# esp32.net
KiCad netlist of a schematic drawn in Altium Designer
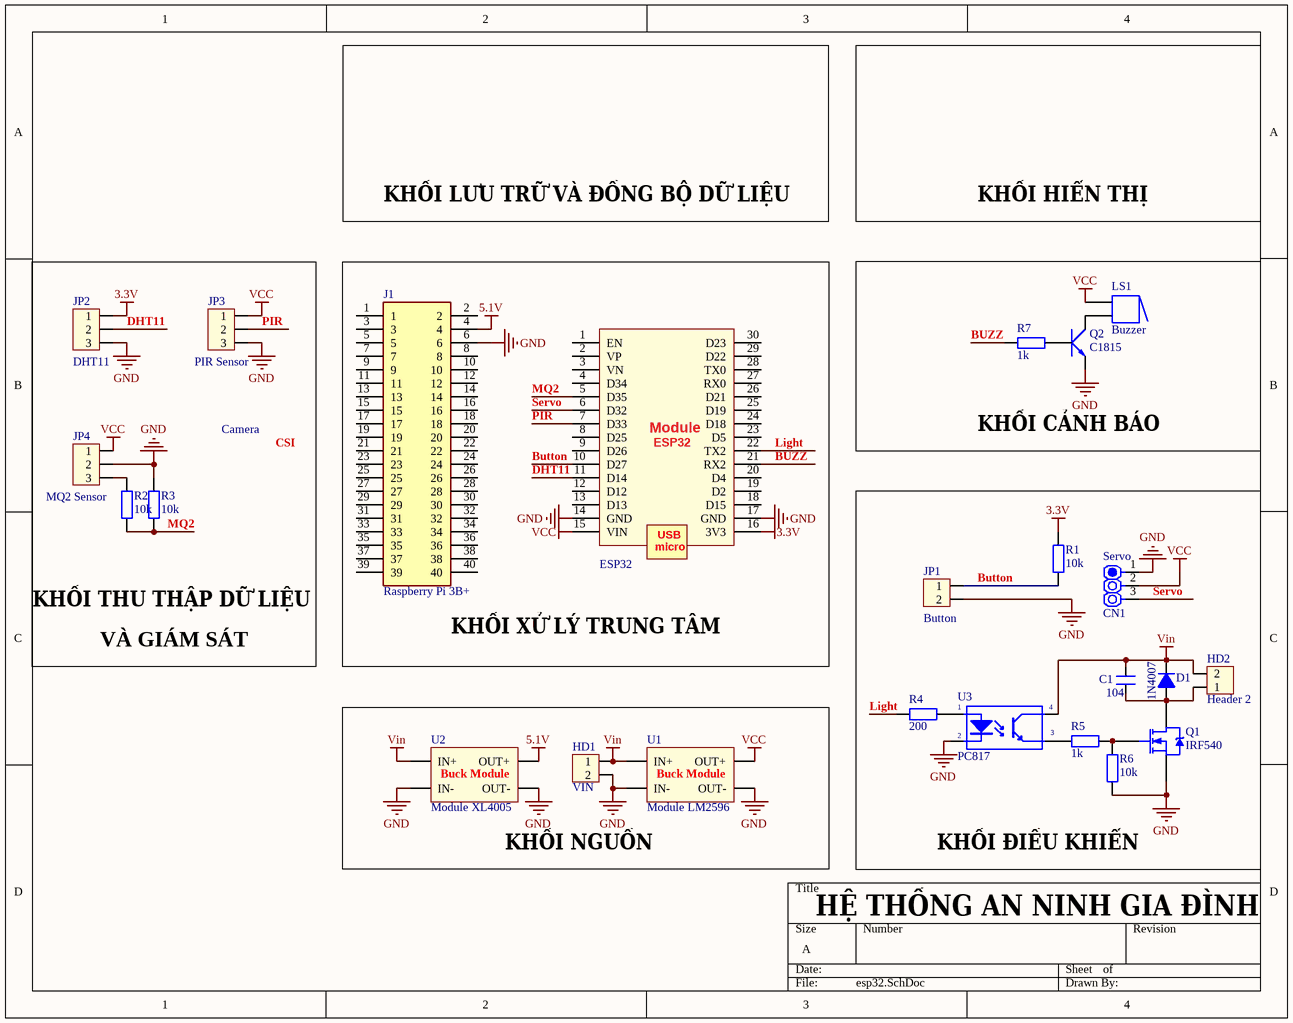
[diagram p0: esp32.SchDoc]

(export (version "E")
  (design (tool "Eeschema 10.0.6"))
  (components
    (comp (ref "C1")
      (value "104")
      (footprint "CN3")
      (description "Cap np W0.3")
      (fields (field (name "COPYRIGHT") "VanDungEvn"))
      (libsource (lib "hphonglib") (part "CN3"))
    )
    (comp (ref "CN1")
      (value "Servo")
      (footprint "CON.HDR1X3")
      (description "Header 1x3")
      (fields (field (name "PUBLISHER") "Hoang Nguyen"))
      (libsource (lib "hphonglib") (part "CON.HDR1x3"))
    )
    (comp (ref "D1")
      (value "1N4007")
      (footprint "D1A")
      (description "Diode 1A")
      (libsource (lib "hphonglib") (part "D1A"))
    )
    (comp (ref "ESP32")
      (value "ESP32_Dev_Module")
      (footprint "ESP32_Dev_Module")
      (libsource (lib "DaoTakIsaac") (part "ESP32_Dev_Module"))
    )
    (comp (ref "HD1")
      (value "VIN")
      (footprint "HED2")
      (description "Header 2 (Green)")
      (libsource (lib "hphonglib") (part "Hed2"))
    )
    (comp (ref "HD2")
      (value "Header 2")
      (footprint "HED2")
      (description "Header 2 (Green)")
      (libsource (lib "") (part "Hed2_1"))
    )
    (comp (ref "J1")
      (value "Raspberry Pi 3B+")
      (footprint "SamacSys:2187")
      (description "Connector")
      (fields (field (name "MANUFACTURER_PART_NUMBER") "2187") (field (name "MOUSER PART NUMBER") "485-2187"))
      (libsource (lib "*") (part "2187"))
    )
    (comp (ref "JP1")
      (value "Button")
      (footprint "CON2")
      (description "Connector 2")
      (libsource (lib "hphonglib") (part "Con2"))
    )
    (comp (ref "JP2")
      (value "DHT11")
      (footprint "CON3")
      (description "Connector 3")
      (libsource (lib "hphonglib") (part "Con3"))
    )
    (comp (ref "JP3")
      (value "PIR Sensor")
      (footprint "CON3")
      (description "Connector 3")
      (libsource (lib "hphonglib") (part "Con3"))
    )
    (comp (ref "JP4")
      (value "MQ2 Sensor")
      (footprint "CON3")
      (description "Connector 3")
      (libsource (lib "hphonglib") (part "Con3"))
    )
    (comp (ref "LS1")
      (value "Buzzer")
      (footprint "Buzzer")
      (description "Magnetic Transducer Buzzer")
      (fields (field (name "PUBLISHER") "Altium Limited"))
      (libsource (lib "hphonglib") (part "Buzzer"))
    )
    (comp (ref "Q1")
      (value "IRF540")
      (footprint "TO-220-3")
      (description "HEXFET N-Channel Power MOSFET")
      (fields (field (name "PUBLISHER") "Altium Limited"))
      (libsource (lib "hphonglib") (part "IRF540"))
    )
    (comp (ref "Q2")
      (value "C1815")
      (footprint "QTO-92")
      (description "NPN 600mW, ECB")
      (libsource (lib "hphonglib") (part "C1815_1"))
    )
    (comp (ref "R1")
      (value "10k")
      (footprint "R1/4W")
      (description "Resistor 1/4W")
      (libsource (lib "hphonglib") (part "R1/4W"))
    )
    (comp (ref "R2")
      (value "10k")
      (footprint "R1/4W")
      (description "Resistor 1/4W")
      (libsource (lib "hphonglib") (part "R1/4W"))
    )
    (comp (ref "R3")
      (value "10k")
      (footprint "R1/4W")
      (description "Resistor 1/4W")
      (libsource (lib "hphonglib") (part "R1/4W"))
    )
    (comp (ref "R4")
      (value "200")
      (footprint "R1/4W")
      (description "Resistor 1/4W")
      (libsource (lib "hphonglib") (part "R1/4W"))
    )
    (comp (ref "R5")
      (value "1k")
      (footprint "R1/4W")
      (description "Resistor 1/4W")
      (libsource (lib "hphonglib") (part "R1/4W"))
    )
    (comp (ref "R6")
      (value "10k")
      (footprint "R1/4W")
      (description "Resistor 1/4W")
      (libsource (lib "hphonglib") (part "R1/4W"))
    )
    (comp (ref "R7")
      (value "1k")
      (footprint "R1/4W")
      (description "Resistor 1/4W")
      (libsource (lib "hphonglib") (part "R1/4W"))
    )
    (comp (ref "U1")
      (value "Module LM2596")
      (footprint "Buck LM2596 Module")
      (description "Buck Module")
      (libsource (lib "DaoTakIsaac") (part "Buck_Module"))
    )
    (comp (ref "U2")
      (value "Module XL4005")
      (footprint "Buck XL4015 Module")
      (description "Buck Module")
      (libsource (lib "DaoTakIsaac") (part "Buck_Module"))
    )
    (comp (ref "U3")
      (value "PC817")
      (footprint "DIP4/W0.3")
      (description "Single Opto")
      (libsource (lib "hphonglib") (part "PC817_1"))
    )
  )
  (nets
    (net (code "1") (name "/BUZZ") (class "Default")
      (node (ref "ESP32") (pin "21") (pinfunction "RX2_21") (pintype "passive"))
      (node (ref "R7") (pin "1") (pinfunction "1_1") (pintype "passive"))
    )
    (net (code "2") (name "/Button") (class "Default")
      (node (ref "ESP32") (pin "10") (pinfunction "D27_10") (pintype "passive"))
      (node (ref "JP1") (pin "1") (pinfunction "1_1") (pintype "passive"))
      (node (ref "R1") (pin "1") (pinfunction "1_1") (pintype "passive"))
    )
    (net (code "4") (name "/DHT11") (class "Default")
      (node (ref "ESP32") (pin "11") (pinfunction "D14_11") (pintype "passive"))
      (node (ref "JP2") (pin "2") (pinfunction "2_2") (pintype "passive"))
    )
    (net (code "5") (name "/Light") (class "Default")
      (node (ref "ESP32") (pin "22") (pinfunction "TX2_22") (pintype "passive"))
      (node (ref "R4") (pin "1") (pinfunction "1_1") (pintype "passive"))
    )
    (net (code "6") (name "/MQ2") (class "Default")
      (node (ref "ESP32") (pin "5") (pinfunction "D35_5") (pintype "passive"))
      (node (ref "R2") (pin "1") (pinfunction "1_1") (pintype "passive"))
      (node (ref "R3") (pin "1") (pinfunction "1_1") (pintype "passive"))
    )
    (net (code "7") (name "/PIR") (class "Default")
      (node (ref "ESP32") (pin "7") (pinfunction "D33_7") (pintype "passive"))
      (node (ref "JP3") (pin "2") (pinfunction "2_2") (pintype "passive"))
    )
    (net (code "8") (name "/Servo") (class "Default")
      (node (ref "CN1") (pin "3") (pinfunction "3_3") (pintype "passive"))
      (node (ref "ESP32") (pin "6") (pinfunction "D32_6") (pintype "passive"))
    )
    (net (code "9") (name "3.3V") (class "Default")
      (node (ref "ESP32") (pin "16") (pinfunction "3V3_16") (pintype "passive"))
      (node (ref "JP2") (pin "1") (pinfunction "1_1") (pintype "passive"))
      (node (ref "R1") (pin "2") (pinfunction "2_2") (pintype "passive"))
    )
    (net (code "10") (name "5.1V") (class "Default")
      (node (ref "J1") (pin "4") (pinfunction "4_4") (pintype "passive"))
      (node (ref "U2") (pin "2") (pinfunction "OUT+_2") (pintype "passive"))
    )
    (net (code "11") (name "GND") (class "Default")
      (node (ref "CN1") (pin "1") (pinfunction "1_1") (pintype "passive"))
      (node (ref "ESP32") (pin "14") (pinfunction "GND_14") (pintype "passive"))
      (node (ref "ESP32") (pin "17") (pinfunction "GND_17") (pintype "passive"))
      (node (ref "HD1") (pin "2") (pinfunction "2_2") (pintype "passive"))
      (node (ref "J1") (pin "6") (pinfunction "6_6") (pintype "passive"))
      (node (ref "JP1") (pin "2") (pinfunction "2_2") (pintype "passive"))
      (node (ref "JP2") (pin "3") (pinfunction "3_3") (pintype "passive"))
      (node (ref "JP3") (pin "3") (pinfunction "3_3") (pintype "passive"))
      (node (ref "JP4") (pin "2") (pinfunction "2_2") (pintype "passive"))
      (node (ref "Q1") (pin "3") (pinfunction "S_3") (pintype "passive"))
      (node (ref "Q2") (pin "1") (pinfunction "E_1") (pintype "passive"))
      (node (ref "R3") (pin "2") (pinfunction "2_2") (pintype "passive"))
      (node (ref "R6") (pin "1") (pinfunction "1_1") (pintype "passive"))
      (node (ref "U1") (pin "3") (pinfunction "IN-_3") (pintype "passive"))
      (node (ref "U1") (pin "4") (pinfunction "OUT-_4") (pintype "passive"))
      (node (ref "U2") (pin "3") (pinfunction "IN-_3") (pintype "passive"))
      (node (ref "U2") (pin "4") (pinfunction "OUT-_4") (pintype "passive"))
      (node (ref "U3") (pin "2") (pinfunction "K_2") (pintype "passive"))
    )
    (net (code "12") (name "Net-(D1-A)") (class "Default")
      (node (ref "C1") (pin "1") (pinfunction "1_1") (pintype "passive"))
      (node (ref "D1") (pin "1") (pinfunction "A_1") (pintype "passive"))
      (node (ref "HD2") (pin "1") (pinfunction "1_1") (pintype "passive"))
      (node (ref "Q1") (pin "2") (pinfunction "D_2") (pintype "passive"))
    )
    (net (code "13") (name "Net-(JP4-Pad3)") (class "Default")
      (node (ref "JP4") (pin "3") (pinfunction "3_3") (pintype "passive"))
      (node (ref "R2") (pin "2") (pinfunction "2_2") (pintype "passive"))
    )
    (net (code "14") (name "Net-(Q1-G)") (class "Default")
      (node (ref "Q1") (pin "1") (pinfunction "G_1") (pintype "passive"))
      (node (ref "R5") (pin "2") (pinfunction "2_2") (pintype "passive"))
      (node (ref "R6") (pin "2") (pinfunction "2_2") (pintype "passive"))
    )
    (net (code "15") (name "Net-(Q2-B)") (class "Default")
      (node (ref "Q2") (pin "3") (pinfunction "B_3") (pintype "passive"))
      (node (ref "R7") (pin "2") (pinfunction "2_2") (pintype "passive"))
    )
    (net (code "16") (name "Net-(Q2-C)") (class "Default")
      (node (ref "LS1") (pin "2") (pinfunction "2_2") (pintype "passive"))
      (node (ref "Q2") (pin "2") (pinfunction "C_2") (pintype "passive"))
    )
    (net (code "17") (name "Net-(U3-A)") (class "Default")
      (node (ref "R4") (pin "2") (pinfunction "2_2") (pintype "passive"))
      (node (ref "U3") (pin "1") (pinfunction "A_1") (pintype "passive"))
    )
    (net (code "18") (name "Net-(U3-E)") (class "Default")
      (node (ref "R5") (pin "1") (pinfunction "1_1") (pintype "passive"))
      (node (ref "U3") (pin "3") (pinfunction "E_3") (pintype "passive"))
    )
    (net (code "19") (name "VCC") (class "Default")
      (node (ref "CN1") (pin "2") (pinfunction "2_2") (pintype "passive"))
      (node (ref "ESP32") (pin "15") (pinfunction "VIN_15") (pintype "passive"))
      (node (ref "JP3") (pin "1") (pinfunction "1_1") (pintype "passive"))
      (node (ref "JP4") (pin "1") (pinfunction "1_1") (pintype "passive"))
      (node (ref "LS1") (pin "1") (pinfunction "1_1") (pintype "passive"))
      (node (ref "U1") (pin "2") (pinfunction "OUT+_2") (pintype "passive"))
    )
    (net (code "20") (name "Vin") (class "Default")
      (node (ref "C1") (pin "2") (pinfunction "2_2") (pintype "passive"))
      (node (ref "D1") (pin "2") (pinfunction "K_2") (pintype "passive"))
      (node (ref "HD1") (pin "1") (pinfunction "1_1") (pintype "passive"))
      (node (ref "HD2") (pin "2") (pinfunction "2_2") (pintype "passive"))
      (node (ref "U1") (pin "1") (pinfunction "IN+_1") (pintype "passive"))
      (node (ref "U2") (pin "1") (pinfunction "IN+_1") (pintype "passive"))
      (node (ref "U3") (pin "4") (pinfunction "C_4") (pintype "passive"))
    )
    (net (code "21") (name "unconnected-(ESP32-D2-Pad19)") (class "Default")
      (node (ref "ESP32") (pin "19") (pinfunction "D2_19") (pintype "passive"))
    )
    (net (code "22") (name "unconnected-(ESP32-D4-Pad20)") (class "Default")
      (node (ref "ESP32") (pin "20") (pinfunction "D4_20") (pintype "passive"))
    )
    (net (code "23") (name "unconnected-(ESP32-D5-Pad23)") (class "Default")
      (node (ref "ESP32") (pin "23") (pinfunction "D5_23") (pintype "passive"))
    )
    (net (code "24") (name "unconnected-(ESP32-D12-Pad12)") (class "Default")
      (node (ref "ESP32") (pin "12") (pinfunction "D12_12") (pintype "passive"))
    )
    (net (code "25") (name "unconnected-(ESP32-D13-Pad13)") (class "Default")
      (node (ref "ESP32") (pin "13") (pinfunction "D13_13") (pintype "passive"))
    )
    (net (code "26") (name "unconnected-(ESP32-D15-Pad18)") (class "Default")
      (node (ref "ESP32") (pin "18") (pinfunction "D15_18") (pintype "passive"))
    )
    (net (code "27") (name "unconnected-(ESP32-D18-Pad24)") (class "Default")
      (node (ref "ESP32") (pin "24") (pinfunction "D18_24") (pintype "passive"))
    )
    (net (code "28") (name "unconnected-(ESP32-D19-Pad25)") (class "Default")
      (node (ref "ESP32") (pin "25") (pinfunction "D19_25") (pintype "passive"))
    )
    (net (code "29") (name "unconnected-(ESP32-D21-Pad26)") (class "Default")
      (node (ref "ESP32") (pin "26") (pinfunction "D21_26") (pintype "passive"))
    )
    (net (code "30") (name "unconnected-(ESP32-D22-Pad29)") (class "Default")
      (node (ref "ESP32") (pin "29") (pinfunction "D22_29") (pintype "passive"))
    )
    (net (code "31") (name "unconnected-(ESP32-D23-Pad30)") (class "Default")
      (node (ref "ESP32") (pin "30") (pinfunction "D23_30") (pintype "passive"))
    )
    (net (code "32") (name "unconnected-(ESP32-D25-Pad8)") (class "Default")
      (node (ref "ESP32") (pin "8") (pinfunction "D25_8") (pintype "passive"))
    )
    (net (code "33") (name "unconnected-(ESP32-D26-Pad9)") (class "Default")
      (node (ref "ESP32") (pin "9") (pinfunction "D26_9") (pintype "passive"))
    )
    (net (code "34") (name "unconnected-(ESP32-D34-Pad4)") (class "Default")
      (node (ref "ESP32") (pin "4") (pinfunction "D34_4") (pintype "passive"))
    )
    (net (code "35") (name "unconnected-(ESP32-EN-Pad1)") (class "Default")
      (node (ref "ESP32") (pin "1") (pinfunction "EN_1") (pintype "passive"))
    )
    (net (code "36") (name "unconnected-(ESP32-RX0-Pad27)") (class "Default")
      (node (ref "ESP32") (pin "27") (pinfunction "RX0_27") (pintype "passive"))
    )
    (net (code "37") (name "unconnected-(ESP32-TX0-Pad28)") (class "Default")
      (node (ref "ESP32") (pin "28") (pinfunction "TX0_28") (pintype "passive"))
    )
    (net (code "38") (name "unconnected-(ESP32-VN-Pad3)") (class "Default")
      (node (ref "ESP32") (pin "3") (pinfunction "VN_3") (pintype "passive"))
    )
    (net (code "39") (name "unconnected-(ESP32-VP-Pad2)") (class "Default")
      (node (ref "ESP32") (pin "2") (pinfunction "VP_2") (pintype "passive"))
    )
    (net (code "40") (name "unconnected-(J1-Pad1)") (class "Default")
      (node (ref "J1") (pin "1") (pinfunction "1_1") (pintype "passive"))
    )
    (net (code "41") (name "unconnected-(J1-Pad2)") (class "Default")
      (node (ref "J1") (pin "2") (pinfunction "2_2") (pintype "passive"))
    )
    (net (code "42") (name "unconnected-(J1-Pad3)") (class "Default")
      (node (ref "J1") (pin "3") (pinfunction "3_3") (pintype "passive"))
    )
    (net (code "43") (name "unconnected-(J1-Pad5)") (class "Default")
      (node (ref "J1") (pin "5") (pinfunction "5_5") (pintype "passive"))
    )
    (net (code "44") (name "unconnected-(J1-Pad7)") (class "Default")
      (node (ref "J1") (pin "7") (pinfunction "7_7") (pintype "passive"))
    )
    (net (code "45") (name "unconnected-(J1-Pad8)") (class "Default")
      (node (ref "J1") (pin "8") (pinfunction "8_8") (pintype "passive"))
    )
    (net (code "46") (name "unconnected-(J1-Pad9)") (class "Default")
      (node (ref "J1") (pin "9") (pinfunction "9_9") (pintype "passive"))
    )
    (net (code "47") (name "unconnected-(J1-Pad10)") (class "Default")
      (node (ref "J1") (pin "10") (pinfunction "10_10") (pintype "passive"))
    )
    (net (code "48") (name "unconnected-(J1-Pad11)") (class "Default")
      (node (ref "J1") (pin "11") (pinfunction "11_11") (pintype "passive"))
    )
    (net (code "49") (name "unconnected-(J1-Pad12)") (class "Default")
      (node (ref "J1") (pin "12") (pinfunction "12_12") (pintype "passive"))
    )
    (net (code "50") (name "unconnected-(J1-Pad13)") (class "Default")
      (node (ref "J1") (pin "13") (pinfunction "13_13") (pintype "passive"))
    )
    (net (code "51") (name "unconnected-(J1-Pad14)") (class "Default")
      (node (ref "J1") (pin "14") (pinfunction "14_14") (pintype "passive"))
    )
    (net (code "52") (name "unconnected-(J1-Pad15)") (class "Default")
      (node (ref "J1") (pin "15") (pinfunction "15_15") (pintype "passive"))
    )
    (net (code "53") (name "unconnected-(J1-Pad16)") (class "Default")
      (node (ref "J1") (pin "16") (pinfunction "16_16") (pintype "passive"))
    )
    (net (code "54") (name "unconnected-(J1-Pad17)") (class "Default")
      (node (ref "J1") (pin "17") (pinfunction "17_17") (pintype "passive"))
    )
    (net (code "55") (name "unconnected-(J1-Pad18)") (class "Default")
      (node (ref "J1") (pin "18") (pinfunction "18_18") (pintype "passive"))
    )
    (net (code "56") (name "unconnected-(J1-Pad19)") (class "Default")
      (node (ref "J1") (pin "19") (pinfunction "19_19") (pintype "passive"))
    )
    (net (code "57") (name "unconnected-(J1-Pad20)") (class "Default")
      (node (ref "J1") (pin "20") (pinfunction "20_20") (pintype "passive"))
    )
    (net (code "58") (name "unconnected-(J1-Pad21)") (class "Default")
      (node (ref "J1") (pin "21") (pinfunction "21_21") (pintype "passive"))
    )
    (net (code "59") (name "unconnected-(J1-Pad22)") (class "Default")
      (node (ref "J1") (pin "22") (pinfunction "22_22") (pintype "passive"))
    )
    (net (code "60") (name "unconnected-(J1-Pad23)") (class "Default")
      (node (ref "J1") (pin "23") (pinfunction "23_23") (pintype "passive"))
    )
    (net (code "61") (name "unconnected-(J1-Pad24)") (class "Default")
      (node (ref "J1") (pin "24") (pinfunction "24_24") (pintype "passive"))
    )
    (net (code "62") (name "unconnected-(J1-Pad25)") (class "Default")
      (node (ref "J1") (pin "25") (pinfunction "25_25") (pintype "passive"))
    )
    (net (code "63") (name "unconnected-(J1-Pad26)") (class "Default")
      (node (ref "J1") (pin "26") (pinfunction "26_26") (pintype "passive"))
    )
    (net (code "64") (name "unconnected-(J1-Pad27)") (class "Default")
      (node (ref "J1") (pin "27") (pinfunction "27_27") (pintype "passive"))
    )
    (net (code "65") (name "unconnected-(J1-Pad28)") (class "Default")
      (node (ref "J1") (pin "28") (pinfunction "28_28") (pintype "passive"))
    )
    (net (code "66") (name "unconnected-(J1-Pad29)") (class "Default")
      (node (ref "J1") (pin "29") (pinfunction "29_29") (pintype "passive"))
    )
    (net (code "67") (name "unconnected-(J1-Pad30)") (class "Default")
      (node (ref "J1") (pin "30") (pinfunction "30_30") (pintype "passive"))
    )
    (net (code "68") (name "unconnected-(J1-Pad31)") (class "Default")
      (node (ref "J1") (pin "31") (pinfunction "31_31") (pintype "passive"))
    )
    (net (code "69") (name "unconnected-(J1-Pad32)") (class "Default")
      (node (ref "J1") (pin "32") (pinfunction "32_32") (pintype "passive"))
    )
    (net (code "70") (name "unconnected-(J1-Pad33)") (class "Default")
      (node (ref "J1") (pin "33") (pinfunction "33_33") (pintype "passive"))
    )
    (net (code "71") (name "unconnected-(J1-Pad34)") (class "Default")
      (node (ref "J1") (pin "34") (pinfunction "34_34") (pintype "passive"))
    )
    (net (code "72") (name "unconnected-(J1-Pad35)") (class "Default")
      (node (ref "J1") (pin "35") (pinfunction "35_35") (pintype "passive"))
    )
    (net (code "73") (name "unconnected-(J1-Pad36)") (class "Default")
      (node (ref "J1") (pin "36") (pinfunction "36_36") (pintype "passive"))
    )
    (net (code "74") (name "unconnected-(J1-Pad37)") (class "Default")
      (node (ref "J1") (pin "37") (pinfunction "37_37") (pintype "passive"))
    )
    (net (code "75") (name "unconnected-(J1-Pad38)") (class "Default")
      (node (ref "J1") (pin "38") (pinfunction "38_38") (pintype "passive"))
    )
    (net (code "76") (name "unconnected-(J1-Pad39)") (class "Default")
      (node (ref "J1") (pin "39") (pinfunction "39_39") (pintype "passive"))
    )
    (net (code "77") (name "unconnected-(J1-Pad40)") (class "Default")
      (node (ref "J1") (pin "40") (pinfunction "40_40") (pintype "passive"))
    )
  )
)
